# UV-Calibrator-Schematic.net
KiCad netlist of a schematic drawn in Altium Designer
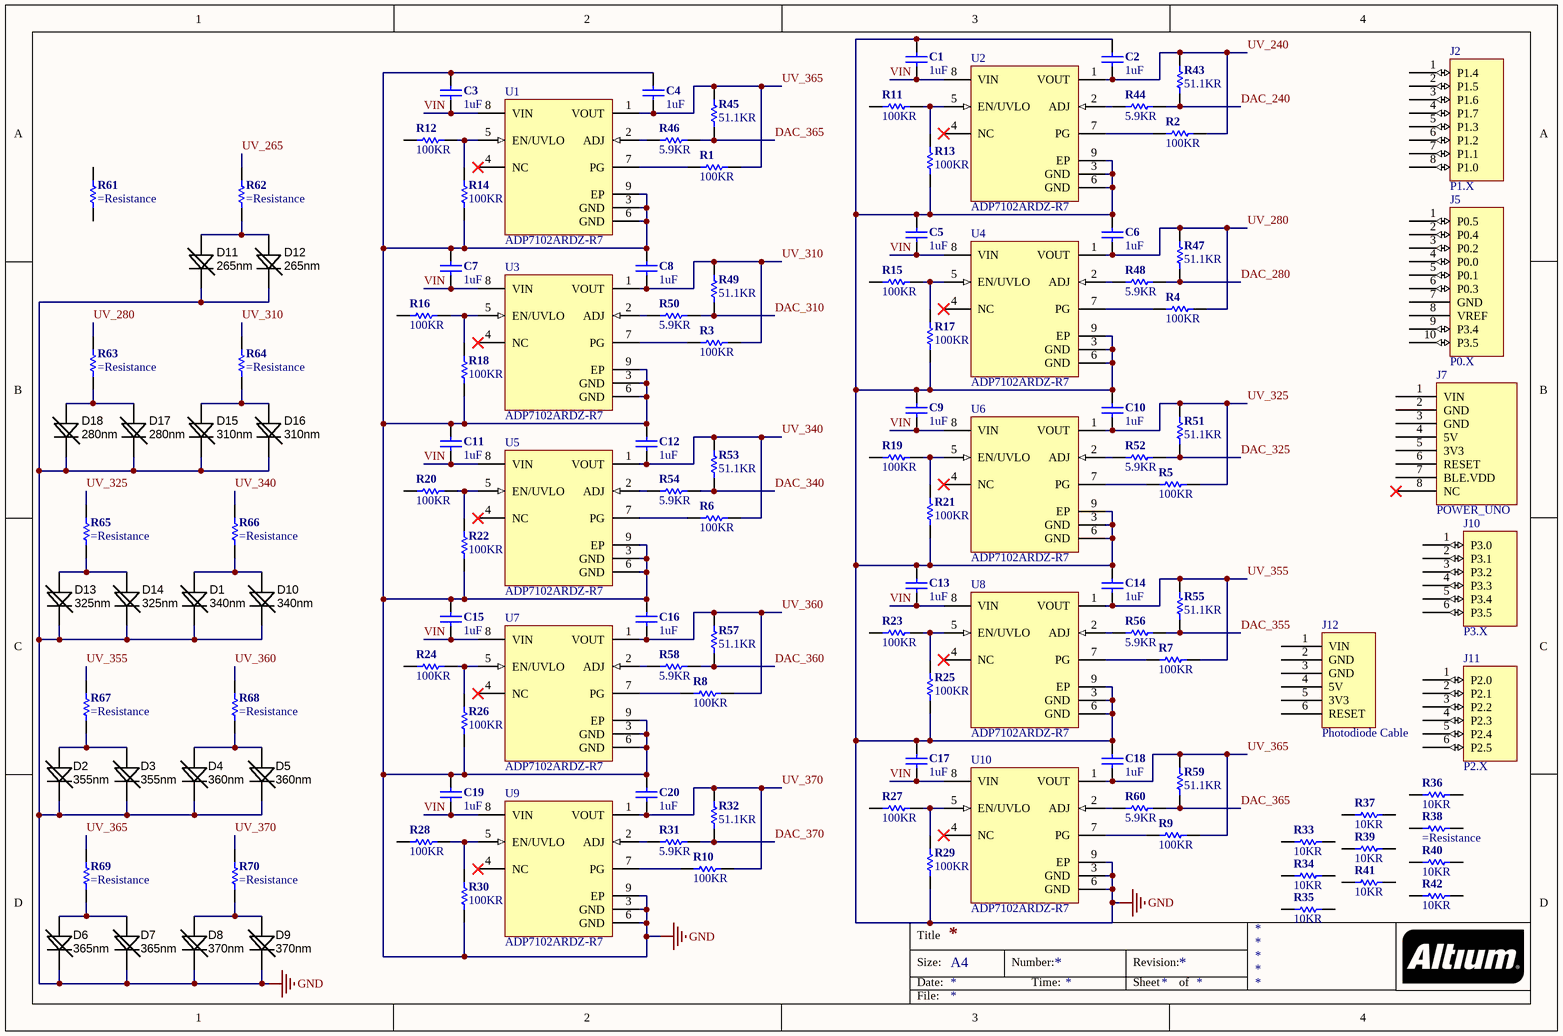
[diagram p0: UV-Calibrator-Schematic.SchDoc]

(export (version "E")
  (design (tool "Eeschema 10.0.6"))
  (components
    (comp (ref "C1")
      (value "1uF")
      (footprint "CAP-0805(2012)-R")
      (description "___ OHM ___ mW 0805(2012) SMD")
      (fields
        (field (name "MANUFACTURER") "Yageo")
        (field (name "MANUFACTURER PART NUMBER") "CC0805KKX7R7BB105")
      )
      (libsource (lib "UVS-Schlib") (part "C-0805(2012)"))
    )
    (comp (ref "C2")
      (value "1uF")
      (footprint "CAP-0805(2012)-R")
      (description "___ OHM ___ mW 0805(2012) SMD")
      (fields
        (field (name "MANUFACTURER") "Yageo")
        (field (name "MANUFACTURER PART NUMBER") "CC0805KKX7R7BB105")
      )
      (libsource (lib "UVS-Schlib") (part "C-0805(2012)"))
    )
    (comp (ref "C3")
      (value "1uF")
      (footprint "CAP-0805(2012)-R")
      (description "___ OHM ___ mW 0805(2012) SMD")
      (fields
        (field (name "MANUFACTURER") "Yageo")
        (field (name "MANUFACTURER PART NUMBER") "CC0805KKX7R7BB105")
      )
      (libsource (lib "UVS-Schlib") (part "C-0805(2012)"))
    )
    (comp (ref "C4")
      (value "1uF")
      (footprint "CAP-0805(2012)-R")
      (description "___ OHM ___ mW 0805(2012) SMD")
      (fields
        (field (name "MANUFACTURER") "Yageo")
        (field (name "MANUFACTURER PART NUMBER") "CC0805KKX7R7BB105")
      )
      (libsource (lib "UVS-Schlib") (part "C-0805(2012)"))
    )
    (comp (ref "C5")
      (value "1uF")
      (footprint "CAP-0805(2012)-R")
      (description "___ OHM ___ mW 0805(2012) SMD")
      (fields
        (field (name "MANUFACTURER") "Yageo")
        (field (name "MANUFACTURER PART NUMBER") "CC0805KKX7R7BB105")
      )
      (libsource (lib "UVS-Schlib") (part "C-0805(2012)"))
    )
    (comp (ref "C6")
      (value "1uF")
      (footprint "CAP-0805(2012)-R")
      (description "___ OHM ___ mW 0805(2012) SMD")
      (fields
        (field (name "MANUFACTURER") "Yageo")
        (field (name "MANUFACTURER PART NUMBER") "CC0805KKX7R7BB105")
      )
      (libsource (lib "UVS-Schlib") (part "C-0805(2012)"))
    )
    (comp (ref "C7")
      (value "1uF")
      (footprint "CAP-0805(2012)-R")
      (description "___ OHM ___ mW 0805(2012) SMD")
      (fields
        (field (name "MANUFACTURER") "Yageo")
        (field (name "MANUFACTURER PART NUMBER") "CC0805KKX7R7BB105")
      )
      (libsource (lib "UVS-Schlib") (part "C-0805(2012)"))
    )
    (comp (ref "C8")
      (value "1uF")
      (footprint "CAP-0805(2012)-R")
      (description "___ OHM ___ mW 0805(2012) SMD")
      (fields
        (field (name "MANUFACTURER") "Yageo")
        (field (name "MANUFACTURER PART NUMBER") "CC0805KKX7R7BB105")
      )
      (libsource (lib "UVS-Schlib") (part "C-0805(2012)"))
    )
    (comp (ref "C9")
      (value "1uF")
      (footprint "CAP-0805(2012)-R")
      (description "___ OHM ___ mW 0805(2012) SMD")
      (fields
        (field (name "MANUFACTURER") "Yageo")
        (field (name "MANUFACTURER PART NUMBER") "CC0805KKX7R7BB105")
      )
      (libsource (lib "UVS-Schlib") (part "C-0805(2012)"))
    )
    (comp (ref "C10")
      (value "1uF")
      (footprint "CAP-0805(2012)-R")
      (description "___ OHM ___ mW 0805(2012) SMD")
      (fields
        (field (name "MANUFACTURER") "Yageo")
        (field (name "MANUFACTURER PART NUMBER") "CC0805KKX7R7BB105")
      )
      (libsource (lib "UVS-Schlib") (part "C-0805(2012)"))
    )
    (comp (ref "C11")
      (value "1uF")
      (footprint "CAP-0805(2012)-R")
      (description "___ OHM ___ mW 0805(2012) SMD")
      (fields
        (field (name "MANUFACTURER") "Yageo")
        (field (name "MANUFACTURER PART NUMBER") "CC0805KKX7R7BB105")
      )
      (libsource (lib "UVS-Schlib") (part "C-0805(2012)"))
    )
    (comp (ref "C12")
      (value "1uF")
      (footprint "CAP-0805(2012)-R")
      (description "___ OHM ___ mW 0805(2012) SMD")
      (fields
        (field (name "MANUFACTURER") "Yageo")
        (field (name "MANUFACTURER PART NUMBER") "CC0805KKX7R7BB105")
      )
      (libsource (lib "UVS-Schlib") (part "C-0805(2012)"))
    )
    (comp (ref "C13")
      (value "1uF")
      (footprint "CAP-0805(2012)-R")
      (description "___ OHM ___ mW 0805(2012) SMD")
      (fields
        (field (name "MANUFACTURER") "Yageo")
        (field (name "MANUFACTURER PART NUMBER") "CC0805KKX7R7BB105")
      )
      (libsource (lib "UVS-Schlib") (part "C-0805(2012)"))
    )
    (comp (ref "C14")
      (value "1uF")
      (footprint "CAP-0805(2012)-R")
      (description "___ OHM ___ mW 0805(2012) SMD")
      (fields
        (field (name "MANUFACTURER") "Yageo")
        (field (name "MANUFACTURER PART NUMBER") "CC0805KKX7R7BB105")
      )
      (libsource (lib "UVS-Schlib") (part "C-0805(2012)"))
    )
    (comp (ref "C15")
      (value "1uF")
      (footprint "CAP-0805(2012)-R")
      (description "___ OHM ___ mW 0805(2012) SMD")
      (fields
        (field (name "MANUFACTURER") "Yageo")
        (field (name "MANUFACTURER PART NUMBER") "CC0805KKX7R7BB105")
      )
      (libsource (lib "UVS-Schlib") (part "C-0805(2012)"))
    )
    (comp (ref "C16")
      (value "1uF")
      (footprint "CAP-0805(2012)-R")
      (description "___ OHM ___ mW 0805(2012) SMD")
      (fields
        (field (name "MANUFACTURER") "Yageo")
        (field (name "MANUFACTURER PART NUMBER") "CC0805KKX7R7BB105")
      )
      (libsource (lib "UVS-Schlib") (part "C-0805(2012)"))
    )
    (comp (ref "C17")
      (value "1uF")
      (footprint "CAP-0805(2012)-R")
      (description "___ OHM ___ mW 0805(2012) SMD")
      (fields
        (field (name "MANUFACTURER") "Yageo")
        (field (name "MANUFACTURER PART NUMBER") "CC0805KKX7R7BB105")
      )
      (libsource (lib "UVS-Schlib") (part "C-0805(2012)"))
    )
    (comp (ref "C18")
      (value "1uF")
      (footprint "CAP-0805(2012)-R")
      (description "___ OHM ___ mW 0805(2012) SMD")
      (fields
        (field (name "MANUFACTURER") "Yageo")
        (field (name "MANUFACTURER PART NUMBER") "CC0805KKX7R7BB105")
      )
      (libsource (lib "UVS-Schlib") (part "C-0805(2012)"))
    )
    (comp (ref "C19")
      (value "1uF")
      (footprint "CAP-0805(2012)-R")
      (description "___ OHM ___ mW 0805(2012) SMD")
      (fields
        (field (name "MANUFACTURER") "Yageo")
        (field (name "MANUFACTURER PART NUMBER") "CC0805KKX7R7BB105")
      )
      (libsource (lib "UVS-Schlib") (part "C-0805(2012)"))
    )
    (comp (ref "C20")
      (value "1uF")
      (footprint "CAP-0805(2012)-R")
      (description "___ OHM ___ mW 0805(2012) SMD")
      (fields
        (field (name "MANUFACTURER") "Yageo")
        (field (name "MANUFACTURER PART NUMBER") "CC0805KKX7R7BB105")
      )
      (libsource (lib "UVS-Schlib") (part "C-0805(2012)"))
    )
    (comp (ref "D1")
      (value "340nm")
      (footprint "SMD 3020")
      (description "SMD 3020 UV Wavelength")
      (libsource (lib "UVS-Schlib") (part "DUVxxx-SMD"))
    )
    (comp (ref "D2")
      (value "355nm")
      (footprint "3mm LED")
      (description "LED, Through Hole 3mm")
      (libsource (lib "UVS-Schlib") (part "XSL-365-LED"))
    )
    (comp (ref "D3")
      (value "355nm")
      (footprint "3mm LED")
      (description "LED, Through Hole 3mm")
      (libsource (lib "UVS-Schlib") (part "XSL-365-LED"))
    )
    (comp (ref "D4")
      (value "360nm")
      (footprint "3mm LED")
      (description "LED, Through Hole 3mm")
      (libsource (lib "UVS-Schlib") (part "XSL-365-LED"))
    )
    (comp (ref "D5")
      (value "360nm")
      (footprint "3mm LED")
      (description "LED, Through Hole 3mm")
      (libsource (lib "UVS-Schlib") (part "XSL-365-LED"))
    )
    (comp (ref "D6")
      (value "365nm")
      (footprint "3mm LED")
      (description "LED, Through Hole 3mm")
      (libsource (lib "UVS-Schlib") (part "XSL-365-LED"))
    )
    (comp (ref "D7")
      (value "365nm")
      (footprint "3mm LED")
      (description "LED, Through Hole 3mm")
      (libsource (lib "UVS-Schlib") (part "XSL-365-LED"))
    )
    (comp (ref "D8")
      (value "370nm")
      (footprint "3mm LED")
      (description "LED, Through Hole 3mm")
      (libsource (lib "UVS-Schlib") (part "XSL-365-LED"))
    )
    (comp (ref "D9")
      (value "370nm")
      (footprint "3mm LED")
      (description "LED, Through Hole 3mm")
      (libsource (lib "UVS-Schlib") (part "XSL-365-LED"))
    )
    (comp (ref "D10")
      (value "340nm")
      (footprint "SMD 3020")
      (description "SMD 3020 UV Wavelength")
      (libsource (lib "UVS-Schlib") (part "DUVxxx-SMD"))
    )
    (comp (ref "D11")
      (value "265nm")
      (footprint "SMD 3020")
      (description "SMD 3020 UV Wavelength")
      (libsource (lib "UVS-Schlib") (part "DUVxxx-SMD"))
    )
    (comp (ref "D12")
      (value "265nm")
      (footprint "SMD 3020")
      (description "SMD 3020 UV Wavelength")
      (libsource (lib "UVS-Schlib") (part "DUVxxx-SMD"))
    )
    (comp (ref "D13")
      (value "325nm")
      (footprint "SMD 3020")
      (description "SMD 3020 UV Wavelength")
      (libsource (lib "UVS-Schlib") (part "DUVxxx-SMD"))
    )
    (comp (ref "D14")
      (value "325nm")
      (footprint "SMD 3020")
      (description "SMD 3020 UV Wavelength")
      (libsource (lib "UVS-Schlib") (part "DUVxxx-SMD"))
    )
    (comp (ref "D15")
      (value "310nm")
      (footprint "SMD 3020")
      (description "SMD 3020 UV Wavelength")
      (libsource (lib "UVS-Schlib") (part "DUVxxx-SMD"))
    )
    (comp (ref "D16")
      (value "310nm")
      (footprint "SMD 3020")
      (description "SMD 3020 UV Wavelength")
      (libsource (lib "UVS-Schlib") (part "DUVxxx-SMD"))
    )
    (comp (ref "D17")
      (value "280nm")
      (footprint "SMD 3020")
      (description "SMD 3020 UV Wavelength")
      (libsource (lib "UVS-Schlib") (part "DUVxxx-SMD"))
    )
    (comp (ref "D18")
      (value "280nm")
      (footprint "SMD 3020")
      (description "SMD 3020 UV Wavelength")
      (libsource (lib "UVS-Schlib") (part "DUVxxx-SMD"))
    )
    (comp (ref "J2")
      (value "P1.X")
      (footprint "Header 8x1 8.5mm")
      (libsource (lib "UVS-Schlib") (part "IOL"))
    )
    (comp (ref "J5")
      (value "P0.X")
      (footprint "Header 10x1 8.5mm")
      (libsource (lib "UVS-Schlib") (part "IOH"))
    )
    (comp (ref "J7")
      (value "POWER_UNO")
      (footprint "Header 8x1 8.5mm")
      (libsource (lib "UVS-Schlib") (part "POWER_UNO"))
    )
    (comp (ref "J10")
      (value "P3.X")
      (footprint "Header 6x1 8.5mm")
      (libsource (lib "UVS-Schlib") (part "AD"))
    )
    (comp (ref "J11")
      (value "P2.X")
      (footprint "Header 6x1 8.5mm")
      (libsource (lib "UVS-Schlib") (part "P2.X"))
    )
    (comp (ref "J12")
      (value "Photodiode Cable")
      (footprint "Header 6x1 8.5mm")
      (libsource (lib "UVS-Schlib") (part "PD_Calibration"))
    )
    (comp (ref "R1")
      (value "100KR")
      (footprint "R-0805(2012)-R")
      (description "___ OHM ___ mW 0805(2012) SMD")
      (fields
        (field (name "MANUFACTURER") "Yageo")
        (field (name "MANUFACTURER PART NUMBER") "RC0805FR-07100KL")
      )
      (libsource (lib "UVS-Schlib") (part "R-0805(2012)"))
    )
    (comp (ref "R2")
      (value "100KR")
      (footprint "R-0805(2012)-R")
      (description "___ OHM ___ mW 0805(2012) SMD")
      (fields
        (field (name "MANUFACTURER") "Yageo")
        (field (name "MANUFACTURER PART NUMBER") "RC0805FR-07100KL")
      )
      (libsource (lib "UVS-Schlib") (part "R-0805(2012)"))
    )
    (comp (ref "R3")
      (value "100KR")
      (footprint "R-0805(2012)-R")
      (description "___ OHM ___ mW 0805(2012) SMD")
      (fields
        (field (name "MANUFACTURER") "Yageo")
        (field (name "MANUFACTURER PART NUMBER") "RC0805FR-07100KL")
      )
      (libsource (lib "UVS-Schlib") (part "R-0805(2012)"))
    )
    (comp (ref "R4")
      (value "100KR")
      (footprint "R-0805(2012)-R")
      (description "___ OHM ___ mW 0805(2012) SMD")
      (fields
        (field (name "MANUFACTURER") "Yageo")
        (field (name "MANUFACTURER PART NUMBER") "RC0805FR-07100KL")
      )
      (libsource (lib "UVS-Schlib") (part "R-0805(2012)"))
    )
    (comp (ref "R5")
      (value "100KR")
      (footprint "R-0805(2012)-R")
      (description "___ OHM ___ mW 0805(2012) SMD")
      (fields
        (field (name "MANUFACTURER") "Yageo")
        (field (name "MANUFACTURER PART NUMBER") "RC0805FR-07100KL")
      )
      (libsource (lib "UVS-Schlib") (part "R-0805(2012)"))
    )
    (comp (ref "R6")
      (value "100KR")
      (footprint "R-0805(2012)-R")
      (description "___ OHM ___ mW 0805(2012) SMD")
      (fields
        (field (name "MANUFACTURER") "Yageo")
        (field (name "MANUFACTURER PART NUMBER") "RC0805FR-07100KL")
      )
      (libsource (lib "UVS-Schlib") (part "R-0805(2012)"))
    )
    (comp (ref "R7")
      (value "100KR")
      (footprint "R-0805(2012)-R")
      (description "___ OHM ___ mW 0805(2012) SMD")
      (fields
        (field (name "MANUFACTURER") "Yageo")
        (field (name "MANUFACTURER PART NUMBER") "RC0805FR-07100KL")
      )
      (libsource (lib "UVS-Schlib") (part "R-0805(2012)"))
    )
    (comp (ref "R8")
      (value "100KR")
      (footprint "R-0805(2012)-R")
      (description "___ OHM ___ mW 0805(2012) SMD")
      (fields
        (field (name "MANUFACTURER") "Yageo")
        (field (name "MANUFACTURER PART NUMBER") "RC0805FR-07100KL")
      )
      (libsource (lib "UVS-Schlib") (part "R-0805(2012)"))
    )
    (comp (ref "R9")
      (value "100KR")
      (footprint "R-0805(2012)-R")
      (description "___ OHM ___ mW 0805(2012) SMD")
      (fields
        (field (name "MANUFACTURER") "Yageo")
        (field (name "MANUFACTURER PART NUMBER") "RC0805FR-07100KL")
      )
      (libsource (lib "UVS-Schlib") (part "R-0805(2012)"))
    )
    (comp (ref "R10")
      (value "100KR")
      (footprint "R-0805(2012)-R")
      (description "___ OHM ___ mW 0805(2012) SMD")
      (fields
        (field (name "MANUFACTURER") "Yageo")
        (field (name "MANUFACTURER PART NUMBER") "RC0805FR-07100KL")
      )
      (libsource (lib "UVS-Schlib") (part "R-0805(2012)"))
    )
    (comp (ref "R11")
      (value "100KR")
      (footprint "R-0805(2012)-R")
      (description "___ OHM ___ mW 0805(2012) SMD")
      (fields
        (field (name "MANUFACTURER") "Yageo")
        (field (name "MANUFACTURER PART NUMBER") "RC0805FR-07100KL")
      )
      (libsource (lib "UVS-Schlib") (part "R-0805(2012)"))
    )
    (comp (ref "R12")
      (value "100KR")
      (footprint "R-0805(2012)-R")
      (description "___ OHM ___ mW 0805(2012) SMD")
      (fields
        (field (name "MANUFACTURER") "Yageo")
        (field (name "MANUFACTURER PART NUMBER") "RC0805FR-07100KL")
      )
      (libsource (lib "UVS-Schlib") (part "R-0805(2012)"))
    )
    (comp (ref "R13")
      (value "100KR")
      (footprint "R-0805(2012)-R")
      (description "___ OHM ___ mW 0805(2012) SMD")
      (fields
        (field (name "MANUFACTURER") "Yageo")
        (field (name "MANUFACTURER PART NUMBER") "RC0805FR-07100KL")
      )
      (libsource (lib "UVS-Schlib") (part "R-0805(2012)"))
    )
    (comp (ref "R14")
      (value "100KR")
      (footprint "R-0805(2012)-R")
      (description "___ OHM ___ mW 0805(2012) SMD")
      (fields
        (field (name "MANUFACTURER") "Yageo")
        (field (name "MANUFACTURER PART NUMBER") "RC0805FR-07100KL")
      )
      (libsource (lib "UVS-Schlib") (part "R-0805(2012)"))
    )
    (comp (ref "R15")
      (value "100KR")
      (footprint "R-0805(2012)-R")
      (description "___ OHM ___ mW 0805(2012) SMD")
      (fields
        (field (name "MANUFACTURER") "Yageo")
        (field (name "MANUFACTURER PART NUMBER") "RC0805FR-07100KL")
      )
      (libsource (lib "UVS-Schlib") (part "R-0805(2012)"))
    )
    (comp (ref "R16")
      (value "100KR")
      (footprint "R-0805(2012)-R")
      (description "___ OHM ___ mW 0805(2012) SMD")
      (fields
        (field (name "MANUFACTURER") "Yageo")
        (field (name "MANUFACTURER PART NUMBER") "RC0805FR-07100KL")
      )
      (libsource (lib "UVS-Schlib") (part "R-0805(2012)"))
    )
    (comp (ref "R17")
      (value "100KR")
      (footprint "R-0805(2012)-R")
      (description "___ OHM ___ mW 0805(2012) SMD")
      (fields
        (field (name "MANUFACTURER") "Yageo")
        (field (name "MANUFACTURER PART NUMBER") "RC0805FR-07100KL")
      )
      (libsource (lib "UVS-Schlib") (part "R-0805(2012)"))
    )
    (comp (ref "R18")
      (value "100KR")
      (footprint "R-0805(2012)-R")
      (description "___ OHM ___ mW 0805(2012) SMD")
      (fields
        (field (name "MANUFACTURER") "Yageo")
        (field (name "MANUFACTURER PART NUMBER") "RC0805FR-07100KL")
      )
      (libsource (lib "UVS-Schlib") (part "R-0805(2012)"))
    )
    (comp (ref "R19")
      (value "100KR")
      (footprint "R-0805(2012)-R")
      (description "___ OHM ___ mW 0805(2012) SMD")
      (fields
        (field (name "MANUFACTURER") "Yageo")
        (field (name "MANUFACTURER PART NUMBER") "RC0805FR-07100KL")
      )
      (libsource (lib "UVS-Schlib") (part "R-0805(2012)"))
    )
    (comp (ref "R20")
      (value "100KR")
      (footprint "R-0805(2012)-R")
      (description "___ OHM ___ mW 0805(2012) SMD")
      (fields
        (field (name "MANUFACTURER") "Yageo")
        (field (name "MANUFACTURER PART NUMBER") "RC0805FR-07100KL")
      )
      (libsource (lib "UVS-Schlib") (part "R-0805(2012)"))
    )
    (comp (ref "R21")
      (value "100KR")
      (footprint "R-0805(2012)-R")
      (description "___ OHM ___ mW 0805(2012) SMD")
      (fields
        (field (name "MANUFACTURER") "Yageo")
        (field (name "MANUFACTURER PART NUMBER") "RC0805FR-07100KL")
      )
      (libsource (lib "UVS-Schlib") (part "R-0805(2012)"))
    )
    (comp (ref "R22")
      (value "100KR")
      (footprint "R-0805(2012)-R")
      (description "___ OHM ___ mW 0805(2012) SMD")
      (fields
        (field (name "MANUFACTURER") "Yageo")
        (field (name "MANUFACTURER PART NUMBER") "RC0805FR-07100KL")
      )
      (libsource (lib "UVS-Schlib") (part "R-0805(2012)"))
    )
    (comp (ref "R23")
      (value "100KR")
      (footprint "R-0805(2012)-R")
      (description "___ OHM ___ mW 0805(2012) SMD")
      (fields
        (field (name "MANUFACTURER") "Yageo")
        (field (name "MANUFACTURER PART NUMBER") "RC0805FR-07100KL")
      )
      (libsource (lib "UVS-Schlib") (part "R-0805(2012)"))
    )
    (comp (ref "R24")
      (value "100KR")
      (footprint "R-0805(2012)-R")
      (description "___ OHM ___ mW 0805(2012) SMD")
      (fields
        (field (name "MANUFACTURER") "Yageo")
        (field (name "MANUFACTURER PART NUMBER") "RC0805FR-07100KL")
      )
      (libsource (lib "UVS-Schlib") (part "R-0805(2012)"))
    )
    (comp (ref "R25")
      (value "100KR")
      (footprint "R-0805(2012)-R")
      (description "___ OHM ___ mW 0805(2012) SMD")
      (fields
        (field (name "MANUFACTURER") "Yageo")
        (field (name "MANUFACTURER PART NUMBER") "RC0805FR-07100KL")
      )
      (libsource (lib "UVS-Schlib") (part "R-0805(2012)"))
    )
    (comp (ref "R26")
      (value "100KR")
      (footprint "R-0805(2012)-R")
      (description "___ OHM ___ mW 0805(2012) SMD")
      (fields
        (field (name "MANUFACTURER") "Yageo")
        (field (name "MANUFACTURER PART NUMBER") "RC0805FR-07100KL")
      )
      (libsource (lib "UVS-Schlib") (part "R-0805(2012)"))
    )
    (comp (ref "R27")
      (value "100KR")
      (footprint "R-0805(2012)-R")
      (description "___ OHM ___ mW 0805(2012) SMD")
      (fields
        (field (name "MANUFACTURER") "Yageo")
        (field (name "MANUFACTURER PART NUMBER") "RC0805FR-07100KL")
      )
      (libsource (lib "UVS-Schlib") (part "R-0805(2012)"))
    )
    (comp (ref "R28")
      (value "100KR")
      (footprint "R-0805(2012)-R")
      (description "___ OHM ___ mW 0805(2012) SMD")
      (fields
        (field (name "MANUFACTURER") "Yageo")
        (field (name "MANUFACTURER PART NUMBER") "RC0805FR-07100KL")
      )
      (libsource (lib "UVS-Schlib") (part "R-0805(2012)"))
    )
    (comp (ref "R29")
      (value "100KR")
      (footprint "R-0805(2012)-R")
      (description "___ OHM ___ mW 0805(2012) SMD")
      (fields
        (field (name "MANUFACTURER") "Yageo")
        (field (name "MANUFACTURER PART NUMBER") "RC0805FR-07100KL")
      )
      (libsource (lib "UVS-Schlib") (part "R-0805(2012)"))
    )
    (comp (ref "R30")
      (value "100KR")
      (footprint "R-0805(2012)-R")
      (description "___ OHM ___ mW 0805(2012) SMD")
      (fields
        (field (name "MANUFACTURER") "Yageo")
        (field (name "MANUFACTURER PART NUMBER") "RC0805FR-07100KL")
      )
      (libsource (lib "UVS-Schlib") (part "R-0805(2012)"))
    )
    (comp (ref "R31")
      (value "5.9KR")
      (footprint "R-0805(2012)-R")
      (description "___ OHM ___ mW 0805(2012) SMD")
      (fields
        (field (name "MANUFACTURER") "Yageo")
        (field (name "MANUFACTURER PART NUMBER") "RC0805FR-075K9L")
      )
      (libsource (lib "UVS-Schlib") (part "R-0805(2012)"))
    )
    (comp (ref "R32")
      (value "51.1KR")
      (footprint "R-0805(2012)-R")
      (description "___ OHM ___ mW 0805(2012) SMD")
      (fields
        (field (name "MANUFACTURER") "Yageo")
        (field (name "MANUFACTURER PART NUMBER") "RC0805FR-0751K1L")
      )
      (libsource (lib "UVS-Schlib") (part "R-0805(2012)"))
    )
    (comp (ref "R33")
      (value "10KR")
      (footprint "R-0805(2012)-R")
      (description "___ OHM ___ mW 0805(2012) SMD")
      (fields
        (field (name "MANUFACTURER") "Yageo")
        (field (name "MANUFACTURER PART NUMBER") "RC0805FR-0710KL")
      )
      (libsource (lib "UVS-Schlib") (part "R-0805(2012)"))
    )
    (comp (ref "R34")
      (value "10KR")
      (footprint "R-0805(2012)-R")
      (description "___ OHM ___ mW 0805(2012) SMD")
      (fields
        (field (name "MANUFACTURER") "Yageo")
        (field (name "MANUFACTURER PART NUMBER") "RC0805FR-0710KL")
      )
      (libsource (lib "UVS-Schlib") (part "R-0805(2012)"))
    )
    (comp (ref "R35")
      (value "10KR")
      (footprint "R-0805(2012)-R")
      (description "___ OHM ___ mW 0805(2012) SMD")
      (fields
        (field (name "MANUFACTURER") "Yageo")
        (field (name "MANUFACTURER PART NUMBER") "RC0805FR-0710KL")
      )
      (libsource (lib "UVS-Schlib") (part "R-0805(2012)"))
    )
    (comp (ref "R36")
      (value "10KR")
      (footprint "R-0805(2012)-R")
      (description "___ OHM ___ mW 0805(2012) SMD")
      (fields
        (field (name "MANUFACTURER") "Yageo")
        (field (name "MANUFACTURER PART NUMBER") "RC0805FR-0710KL")
      )
      (libsource (lib "UVS-Schlib") (part "R-0805(2012)"))
    )
    (comp (ref "R37")
      (value "10KR")
      (footprint "R-0805(2012)-R")
      (description "___ OHM ___ mW 0805(2012) SMD")
      (fields
        (field (name "MANUFACTURER") "Yageo")
        (field (name "MANUFACTURER PART NUMBER") "RC0805FR-0710KL")
      )
      (libsource (lib "UVS-Schlib") (part "R-0805(2012)"))
    )
    (comp (ref "R38")
      (value "~")
      (footprint "R-0805(2012)-R")
      (description "___ OHM ___ mW 0805(2012) SMD")
      (libsource (lib "UVS-Schlib") (part "R-0805(2012)"))
    )
    (comp (ref "R39")
      (value "10KR")
      (footprint "R-0805(2012)-R")
      (description "___ OHM ___ mW 0805(2012) SMD")
      (fields
        (field (name "MANUFACTURER") "Yageo")
        (field (name "MANUFACTURER PART NUMBER") "RC0805FR-0710KL")
      )
      (libsource (lib "UVS-Schlib") (part "R-0805(2012)"))
    )
    (comp (ref "R40")
      (value "10KR")
      (footprint "R-0805(2012)-R")
      (description "___ OHM ___ mW 0805(2012) SMD")
      (fields
        (field (name "MANUFACTURER") "Yageo")
        (field (name "MANUFACTURER PART NUMBER") "RC0805FR-0710KL")
      )
      (libsource (lib "UVS-Schlib") (part "R-0805(2012)"))
    )
    (comp (ref "R41")
      (value "10KR")
      (footprint "R-0805(2012)-R")
      (description "___ OHM ___ mW 0805(2012) SMD")
      (fields
        (field (name "MANUFACTURER") "Yageo")
        (field (name "MANUFACTURER PART NUMBER") "RC0805FR-0710KL")
      )
      (libsource (lib "UVS-Schlib") (part "R-0805(2012)"))
    )
    (comp (ref "R42")
      (value "10KR")
      (footprint "R-0805(2012)-R")
      (description "___ OHM ___ mW 0805(2012) SMD")
      (fields
        (field (name "MANUFACTURER") "Yageo")
        (field (name "MANUFACTURER PART NUMBER") "RC0805FR-0710KL")
      )
      (libsource (lib "UVS-Schlib") (part "R-0805(2012)"))
    )
    (comp (ref "R43")
      (value "51.1KR")
      (footprint "R-0805(2012)-R")
      (description "___ OHM ___ mW 0805(2012) SMD")
      (fields
        (field (name "MANUFACTURER") "Yageo")
        (field (name "MANUFACTURER PART NUMBER") "RC0805FR-0751K1L")
      )
      (libsource (lib "UVS-Schlib") (part "R-0805(2012)"))
    )
    (comp (ref "R44")
      (value "5.9KR")
      (footprint "R-0805(2012)-R")
      (description "___ OHM ___ mW 0805(2012) SMD")
      (fields
        (field (name "MANUFACTURER") "Yageo")
        (field (name "MANUFACTURER PART NUMBER") "RC0805FR-075K9L")
      )
      (libsource (lib "UVS-Schlib") (part "R-0805(2012)"))
    )
    (comp (ref "R45")
      (value "51.1KR")
      (footprint "R-0805(2012)-R")
      (description "___ OHM ___ mW 0805(2012) SMD")
      (fields
        (field (name "MANUFACTURER") "Yageo")
        (field (name "MANUFACTURER PART NUMBER") "RC0805FR-0751K1L")
      )
      (libsource (lib "UVS-Schlib") (part "R-0805(2012)"))
    )
    (comp (ref "R46")
      (value "5.9KR")
      (footprint "R-0805(2012)-R")
      (description "___ OHM ___ mW 0805(2012) SMD")
      (fields
        (field (name "MANUFACTURER") "Yageo")
        (field (name "MANUFACTURER PART NUMBER") "RC0805FR-075K9L")
      )
      (libsource (lib "UVS-Schlib") (part "R-0805(2012)"))
    )
    (comp (ref "R47")
      (value "51.1KR")
      (footprint "R-0805(2012)-R")
      (description "___ OHM ___ mW 0805(2012) SMD")
      (fields
        (field (name "MANUFACTURER") "Yageo")
        (field (name "MANUFACTURER PART NUMBER") "RC0805FR-0751K1L")
      )
      (libsource (lib "UVS-Schlib") (part "R-0805(2012)"))
    )
    (comp (ref "R48")
      (value "5.9KR")
      (footprint "R-0805(2012)-R")
      (description "___ OHM ___ mW 0805(2012) SMD")
      (fields
        (field (name "MANUFACTURER") "Yageo")
        (field (name "MANUFACTURER PART NUMBER") "RC0805FR-075K9L")
      )
      (libsource (lib "UVS-Schlib") (part "R-0805(2012)"))
    )
    (comp (ref "R49")
      (value "51.1KR")
      (footprint "R-0805(2012)-R")
      (description "___ OHM ___ mW 0805(2012) SMD")
      (fields
        (field (name "MANUFACTURER") "Yageo")
        (field (name "MANUFACTURER PART NUMBER") "RC0805FR-0751K1L")
      )
      (libsource (lib "UVS-Schlib") (part "R-0805(2012)"))
    )
    (comp (ref "R50")
      (value "5.9KR")
      (footprint "R-0805(2012)-R")
      (description "___ OHM ___ mW 0805(2012) SMD")
      (fields
        (field (name "MANUFACTURER") "Yageo")
        (field (name "MANUFACTURER PART NUMBER") "RC0805FR-075K9L")
      )
      (libsource (lib "UVS-Schlib") (part "R-0805(2012)"))
    )
    (comp (ref "R51")
      (value "51.1KR")
      (footprint "R-0805(2012)-R")
      (description "___ OHM ___ mW 0805(2012) SMD")
      (fields
        (field (name "MANUFACTURER") "Yageo")
        (field (name "MANUFACTURER PART NUMBER") "RC0805FR-0751K1L")
      )
      (libsource (lib "UVS-Schlib") (part "R-0805(2012)"))
    )
    (comp (ref "R52")
      (value "5.9KR")
      (footprint "R-0805(2012)-R")
      (description "___ OHM ___ mW 0805(2012) SMD")
      (fields
        (field (name "MANUFACTURER") "Yageo")
        (field (name "MANUFACTURER PART NUMBER") "RC0805FR-075K9L")
      )
      (libsource (lib "UVS-Schlib") (part "R-0805(2012)"))
    )
    (comp (ref "R53")
      (value "51.1KR")
      (footprint "R-0805(2012)-R")
      (description "___ OHM ___ mW 0805(2012) SMD")
      (fields
        (field (name "MANUFACTURER") "Yageo")
        (field (name "MANUFACTURER PART NUMBER") "RC0805FR-0751K1L")
      )
      (libsource (lib "UVS-Schlib") (part "R-0805(2012)"))
    )
    (comp (ref "R54")
      (value "5.9KR")
      (footprint "R-0805(2012)-R")
      (description "___ OHM ___ mW 0805(2012) SMD")
      (fields
        (field (name "MANUFACTURER") "Yageo")
        (field (name "MANUFACTURER PART NUMBER") "RC0805FR-075K9L")
      )
      (libsource (lib "UVS-Schlib") (part "R-0805(2012)"))
    )
    (comp (ref "R55")
      (value "51.1KR")
      (footprint "R-0805(2012)-R")
      (description "___ OHM ___ mW 0805(2012) SMD")
      (fields
        (field (name "MANUFACTURER") "Yageo")
        (field (name "MANUFACTURER PART NUMBER") "RC0805FR-0751K1L")
      )
      (libsource (lib "UVS-Schlib") (part "R-0805(2012)"))
    )
    (comp (ref "R56")
      (value "5.9KR")
      (footprint "R-0805(2012)-R")
      (description "___ OHM ___ mW 0805(2012) SMD")
      (fields
        (field (name "MANUFACTURER") "Yageo")
        (field (name "MANUFACTURER PART NUMBER") "RC0805FR-075K9L")
      )
      (libsource (lib "UVS-Schlib") (part "R-0805(2012)"))
    )
    (comp (ref "R57")
      (value "51.1KR")
      (footprint "R-0805(2012)-R")
      (description "___ OHM ___ mW 0805(2012) SMD")
      (fields
        (field (name "MANUFACTURER") "Yageo")
        (field (name "MANUFACTURER PART NUMBER") "RC0805FR-0751K1L")
      )
      (libsource (lib "UVS-Schlib") (part "R-0805(2012)"))
    )
    (comp (ref "R58")
      (value "5.9KR")
      (footprint "R-0805(2012)-R")
      (description "___ OHM ___ mW 0805(2012) SMD")
      (fields
        (field (name "MANUFACTURER") "Yageo")
        (field (name "MANUFACTURER PART NUMBER") "RC0805FR-075K9L")
      )
      (libsource (lib "UVS-Schlib") (part "R-0805(2012)"))
    )
    (comp (ref "R59")
      (value "51.1KR")
      (footprint "R-0805(2012)-R")
      (description "___ OHM ___ mW 0805(2012) SMD")
      (fields
        (field (name "MANUFACTURER") "Yageo")
        (field (name "MANUFACTURER PART NUMBER") "RC0805FR-0751K1L")
      )
      (libsource (lib "UVS-Schlib") (part "R-0805(2012)"))
    )
    (comp (ref "R60")
      (value "5.9KR")
      (footprint "R-0805(2012)-R")
      (description "___ OHM ___ mW 0805(2012) SMD")
      (fields
        (field (name "MANUFACTURER") "Yageo")
        (field (name "MANUFACTURER PART NUMBER") "RC0805FR-075K9L")
      )
      (libsource (lib "UVS-Schlib") (part "R-0805(2012)"))
    )
    (comp (ref "R61")
      (value "~")
      (footprint "R-0805(2012)-R")
      (description "___ OHM ___ mW 0805(2012) SMD")
      (libsource (lib "UVS-Schlib") (part "R-0805(2012)"))
    )
    (comp (ref "R62")
      (value "~")
      (footprint "R-0805(2012)-R")
      (description "___ OHM ___ mW 0805(2012) SMD")
      (libsource (lib "UVS-Schlib") (part "R-0805(2012)"))
    )
    (comp (ref "R63")
      (value "~")
      (footprint "R-0805(2012)-R")
      (description "___ OHM ___ mW 0805(2012) SMD")
      (libsource (lib "UVS-Schlib") (part "R-0805(2012)"))
    )
    (comp (ref "R64")
      (value "~")
      (footprint "R-0805(2012)-R")
      (description "___ OHM ___ mW 0805(2012) SMD")
      (libsource (lib "UVS-Schlib") (part "R-0805(2012)"))
    )
    (comp (ref "R65")
      (value "~")
      (footprint "R-0805(2012)-R")
      (description "___ OHM ___ mW 0805(2012) SMD")
      (libsource (lib "UVS-Schlib") (part "R-0805(2012)"))
    )
    (comp (ref "R66")
      (value "~")
      (footprint "R-0805(2012)-R")
      (description "___ OHM ___ mW 0805(2012) SMD")
      (libsource (lib "UVS-Schlib") (part "R-0805(2012)"))
    )
    (comp (ref "R67")
      (value "~")
      (footprint "R-0805(2012)-R")
      (description "___ OHM ___ mW 0805(2012) SMD")
      (libsource (lib "UVS-Schlib") (part "R-0805(2012)"))
    )
    (comp (ref "R68")
      (value "~")
      (footprint "R-0805(2012)-R")
      (description "___ OHM ___ mW 0805(2012) SMD")
      (libsource (lib "UVS-Schlib") (part "R-0805(2012)"))
    )
    (comp (ref "R69")
      (value "~")
      (footprint "R-0805(2012)-R")
      (description "___ OHM ___ mW 0805(2012) SMD")
      (libsource (lib "UVS-Schlib") (part "R-0805(2012)"))
    )
    (comp (ref "R70")
      (value "~")
      (footprint "R-0805(2012)-R")
      (description "___ OHM ___ mW 0805(2012) SMD")
      (libsource (lib "UVS-Schlib") (part "R-0805(2012)"))
    )
    (comp (ref "U1")
      (value "ADP7102ARDZ-R7")
      (footprint "ADI-RD-8-2_N")
      (fields (field (name "MANUFACTURER") "Analog Devices"))
      (libsource (lib "Altium Content Vault") (part "ADI-ADP7102_A-RD-8-2"))
    )
    (comp (ref "U2")
      (value "ADP7102ARDZ-R7")
      (footprint "ADI-RD-8-2_N")
      (fields (field (name "MANUFACTURER") "Analog Devices"))
      (libsource (lib "Altium Content Vault") (part "ADI-ADP7102_A-RD-8-2"))
    )
    (comp (ref "U3")
      (value "ADP7102ARDZ-R7")
      (footprint "ADI-RD-8-2_N")
      (fields (field (name "MANUFACTURER") "Analog Devices"))
      (libsource (lib "Altium Content Vault") (part "ADI-ADP7102_A-RD-8-2"))
    )
    (comp (ref "U4")
      (value "ADP7102ARDZ-R7")
      (footprint "ADI-RD-8-2_N")
      (fields (field (name "MANUFACTURER") "Analog Devices"))
      (libsource (lib "Altium Content Vault") (part "ADI-ADP7102_A-RD-8-2"))
    )
    (comp (ref "U5")
      (value "ADP7102ARDZ-R7")
      (footprint "ADI-RD-8-2_N")
      (fields (field (name "MANUFACTURER") "Analog Devices"))
      (libsource (lib "Altium Content Vault") (part "ADI-ADP7102_A-RD-8-2"))
    )
    (comp (ref "U6")
      (value "ADP7102ARDZ-R7")
      (footprint "ADI-RD-8-2_N")
      (fields (field (name "MANUFACTURER") "Analog Devices"))
      (libsource (lib "Altium Content Vault") (part "ADI-ADP7102_A-RD-8-2"))
    )
    (comp (ref "U7")
      (value "ADP7102ARDZ-R7")
      (footprint "ADI-RD-8-2_N")
      (fields (field (name "MANUFACTURER") "Analog Devices"))
      (libsource (lib "Altium Content Vault") (part "ADI-ADP7102_A-RD-8-2"))
    )
    (comp (ref "U8")
      (value "ADP7102ARDZ-R7")
      (footprint "ADI-RD-8-2_N")
      (fields (field (name "MANUFACTURER") "Analog Devices"))
      (libsource (lib "Altium Content Vault") (part "ADI-ADP7102_A-RD-8-2"))
    )
    (comp (ref "U9")
      (value "ADP7102ARDZ-R7")
      (footprint "ADI-RD-8-2_N")
      (fields (field (name "MANUFACTURER") "Analog Devices"))
      (libsource (lib "Altium Content Vault") (part "ADI-ADP7102_A-RD-8-2"))
    )
    (comp (ref "U10")
      (value "ADP7102ARDZ-R7")
      (footprint "ADI-RD-8-2_N")
      (fields (field (name "MANUFACTURER") "Analog Devices"))
      (libsource (lib "Altium Content Vault") (part "ADI-ADP7102_A-RD-8-2"))
    )
  )
  (nets
    (net (code "1") (name "/DAC_240") (class "Default")
      (node (ref "R43") (pin "2") (pinfunction "2_2") (pintype "passive"))
      (node (ref "R44") (pin "2") (pinfunction "2_2") (pintype "passive"))
    )
    (net (code "2") (name "/DAC_280") (class "Default")
      (node (ref "R47") (pin "2") (pinfunction "2_2") (pintype "passive"))
      (node (ref "R48") (pin "2") (pinfunction "2_2") (pintype "passive"))
    )
    (net (code "3") (name "/DAC_310") (class "Default")
      (node (ref "R49") (pin "2") (pinfunction "2_2") (pintype "passive"))
      (node (ref "R50") (pin "2") (pinfunction "2_2") (pintype "passive"))
    )
    (net (code "4") (name "/DAC_325") (class "Default")
      (node (ref "R51") (pin "2") (pinfunction "2_2") (pintype "passive"))
      (node (ref "R52") (pin "2") (pinfunction "2_2") (pintype "passive"))
    )
    (net (code "5") (name "/DAC_340") (class "Default")
      (node (ref "R53") (pin "2") (pinfunction "2_2") (pintype "passive"))
      (node (ref "R54") (pin "2") (pinfunction "2_2") (pintype "passive"))
    )
    (net (code "6") (name "/DAC_355") (class "Default")
      (node (ref "R55") (pin "2") (pinfunction "2_2") (pintype "passive"))
      (node (ref "R56") (pin "2") (pinfunction "2_2") (pintype "passive"))
    )
    (net (code "7") (name "/DAC_360") (class "Default")
      (node (ref "R57") (pin "2") (pinfunction "2_2") (pintype "passive"))
      (node (ref "R58") (pin "2") (pinfunction "2_2") (pintype "passive"))
    )
    (net (code "8") (name "/DAC_365") (class "Default")
      (node (ref "R45") (pin "2") (pinfunction "2_2") (pintype "passive"))
      (node (ref "R46") (pin "2") (pinfunction "2_2") (pintype "passive"))
      (node (ref "R59") (pin "2") (pinfunction "2_2") (pintype "passive"))
      (node (ref "R60") (pin "2") (pinfunction "2_2") (pintype "passive"))
    )
    (net (code "9") (name "/DAC_370") (class "Default")
      (node (ref "R31") (pin "2") (pinfunction "2_2") (pintype "passive"))
      (node (ref "R32") (pin "2") (pinfunction "2_2") (pintype "passive"))
    )
    (net (code "10") (name "/UV_240") (class "Default")
      (node (ref "C2") (pin "2") (pinfunction "2_2") (pintype "passive"))
      (node (ref "R2") (pin "2") (pinfunction "2_2") (pintype "passive"))
      (node (ref "R43") (pin "1") (pinfunction "1_1") (pintype "passive"))
      (node (ref "U2") (pin "1") (pinfunction "VOUT_1") (pintype "power_in"))
    )
    (net (code "11") (name "/UV_265") (class "Default")
      (node (ref "R62") (pin "1") (pinfunction "1_1") (pintype "passive"))
    )
    (net (code "12") (name "/UV_280") (class "Default")
      (node (ref "C6") (pin "2") (pinfunction "2_2") (pintype "passive"))
      (node (ref "R4") (pin "2") (pinfunction "2_2") (pintype "passive"))
      (node (ref "R47") (pin "1") (pinfunction "1_1") (pintype "passive"))
      (node (ref "R63") (pin "1") (pinfunction "1_1") (pintype "passive"))
      (node (ref "U4") (pin "1") (pinfunction "VOUT_1") (pintype "power_in"))
    )
    (net (code "13") (name "/UV_310") (class "Default")
      (node (ref "C8") (pin "2") (pinfunction "2_2") (pintype "passive"))
      (node (ref "R3") (pin "2") (pinfunction "2_2") (pintype "passive"))
      (node (ref "R49") (pin "1") (pinfunction "1_1") (pintype "passive"))
      (node (ref "R64") (pin "1") (pinfunction "1_1") (pintype "passive"))
      (node (ref "U3") (pin "1") (pinfunction "VOUT_1") (pintype "power_in"))
    )
    (net (code "14") (name "/UV_325") (class "Default")
      (node (ref "C10") (pin "2") (pinfunction "2_2") (pintype "passive"))
      (node (ref "R5") (pin "2") (pinfunction "2_2") (pintype "passive"))
      (node (ref "R51") (pin "1") (pinfunction "1_1") (pintype "passive"))
      (node (ref "R65") (pin "1") (pinfunction "1_1") (pintype "passive"))
      (node (ref "U6") (pin "1") (pinfunction "VOUT_1") (pintype "power_in"))
    )
    (net (code "15") (name "/UV_340") (class "Default")
      (node (ref "C12") (pin "2") (pinfunction "2_2") (pintype "passive"))
      (node (ref "R53") (pin "1") (pinfunction "1_1") (pintype "passive"))
      (node (ref "R6") (pin "2") (pinfunction "2_2") (pintype "passive"))
      (node (ref "R66") (pin "1") (pinfunction "1_1") (pintype "passive"))
      (node (ref "U5") (pin "1") (pinfunction "VOUT_1") (pintype "power_in"))
    )
    (net (code "16") (name "/UV_355") (class "Default")
      (node (ref "C14") (pin "2") (pinfunction "2_2") (pintype "passive"))
      (node (ref "R55") (pin "1") (pinfunction "1_1") (pintype "passive"))
      (node (ref "R67") (pin "1") (pinfunction "1_1") (pintype "passive"))
      (node (ref "R7") (pin "2") (pinfunction "2_2") (pintype "passive"))
      (node (ref "U8") (pin "1") (pinfunction "VOUT_1") (pintype "power_in"))
    )
    (net (code "17") (name "/UV_360") (class "Default")
      (node (ref "C16") (pin "2") (pinfunction "2_2") (pintype "passive"))
      (node (ref "R57") (pin "1") (pinfunction "1_1") (pintype "passive"))
      (node (ref "R68") (pin "1") (pinfunction "1_1") (pintype "passive"))
      (node (ref "R8") (pin "2") (pinfunction "2_2") (pintype "passive"))
      (node (ref "U7") (pin "1") (pinfunction "VOUT_1") (pintype "power_in"))
    )
    (net (code "18") (name "/UV_365") (class "Default")
      (node (ref "C18") (pin "2") (pinfunction "2_2") (pintype "passive"))
      (node (ref "C4") (pin "2") (pinfunction "2_2") (pintype "passive"))
      (node (ref "R1") (pin "2") (pinfunction "2_2") (pintype "passive"))
      (node (ref "R45") (pin "1") (pinfunction "1_1") (pintype "passive"))
      (node (ref "R59") (pin "1") (pinfunction "1_1") (pintype "passive"))
      (node (ref "R69") (pin "1") (pinfunction "1_1") (pintype "passive"))
      (node (ref "R9") (pin "2") (pinfunction "2_2") (pintype "passive"))
      (node (ref "U1") (pin "1") (pinfunction "VOUT_1") (pintype "power_in"))
      (node (ref "U10") (pin "1") (pinfunction "VOUT_1") (pintype "power_in"))
    )
    (net (code "19") (name "/UV_370") (class "Default")
      (node (ref "C20") (pin "2") (pinfunction "2_2") (pintype "passive"))
      (node (ref "R10") (pin "2") (pinfunction "2_2") (pintype "passive"))
      (node (ref "R32") (pin "1") (pinfunction "1_1") (pintype "passive"))
      (node (ref "R70") (pin "1") (pinfunction "1_1") (pintype "passive"))
      (node (ref "U9") (pin "1") (pinfunction "VOUT_1") (pintype "power_in"))
    )
    (net (code "20") (name "/VIN") (class "Default")
      (node (ref "C1") (pin "2") (pinfunction "2_2") (pintype "passive"))
      (node (ref "C11") (pin "2") (pinfunction "2_2") (pintype "passive"))
      (node (ref "C13") (pin "2") (pinfunction "2_2") (pintype "passive"))
      (node (ref "C15") (pin "2") (pinfunction "2_2") (pintype "passive"))
      (node (ref "C17") (pin "2") (pinfunction "2_2") (pintype "passive"))
      (node (ref "C19") (pin "2") (pinfunction "2_2") (pintype "passive"))
      (node (ref "C3") (pin "2") (pinfunction "2_2") (pintype "passive"))
      (node (ref "C5") (pin "2") (pinfunction "2_2") (pintype "passive"))
      (node (ref "C7") (pin "2") (pinfunction "2_2") (pintype "passive"))
      (node (ref "C9") (pin "2") (pinfunction "2_2") (pintype "passive"))
      (node (ref "U1") (pin "8") (pinfunction "VIN_8") (pintype "power_in"))
      (node (ref "U10") (pin "8") (pinfunction "VIN_8") (pintype "power_in"))
      (node (ref "U2") (pin "8") (pinfunction "VIN_8") (pintype "power_in"))
      (node (ref "U3") (pin "8") (pinfunction "VIN_8") (pintype "power_in"))
      (node (ref "U4") (pin "8") (pinfunction "VIN_8") (pintype "power_in"))
      (node (ref "U5") (pin "8") (pinfunction "VIN_8") (pintype "power_in"))
      (node (ref "U6") (pin "8") (pinfunction "VIN_8") (pintype "power_in"))
      (node (ref "U7") (pin "8") (pinfunction "VIN_8") (pintype "power_in"))
      (node (ref "U8") (pin "8") (pinfunction "VIN_8") (pintype "power_in"))
      (node (ref "U9") (pin "8") (pinfunction "VIN_8") (pintype "power_in"))
    )
    (net (code "21") (name "GND") (class "Default")
      (node (ref "C1") (pin "1") (pinfunction "1_1") (pintype "passive"))
      (node (ref "C10") (pin "1") (pinfunction "1_1") (pintype "passive"))
      (node (ref "C11") (pin "1") (pinfunction "1_1") (pintype "passive"))
      (node (ref "C12") (pin "1") (pinfunction "1_1") (pintype "passive"))
      (node (ref "C13") (pin "1") (pinfunction "1_1") (pintype "passive"))
      (node (ref "C14") (pin "1") (pinfunction "1_1") (pintype "passive"))
      (node (ref "C15") (pin "1") (pinfunction "1_1") (pintype "passive"))
      (node (ref "C16") (pin "1") (pinfunction "1_1") (pintype "passive"))
      (node (ref "C17") (pin "1") (pinfunction "1_1") (pintype "passive"))
      (node (ref "C18") (pin "1") (pinfunction "1_1") (pintype "passive"))
      (node (ref "C19") (pin "1") (pinfunction "1_1") (pintype "passive"))
      (node (ref "C2") (pin "1") (pinfunction "1_1") (pintype "passive"))
      (node (ref "C20") (pin "1") (pinfunction "1_1") (pintype "passive"))
      (node (ref "C3") (pin "1") (pinfunction "1_1") (pintype "passive"))
      (node (ref "C4") (pin "1") (pinfunction "1_1") (pintype "passive"))
      (node (ref "C5") (pin "1") (pinfunction "1_1") (pintype "passive"))
      (node (ref "C6") (pin "1") (pinfunction "1_1") (pintype "passive"))
      (node (ref "C7") (pin "1") (pinfunction "1_1") (pintype "passive"))
      (node (ref "C8") (pin "1") (pinfunction "1_1") (pintype "passive"))
      (node (ref "C9") (pin "1") (pinfunction "1_1") (pintype "passive"))
      (node (ref "D1") (pin "K") (pinfunction "K_K") (pintype "passive"))
      (node (ref "D10") (pin "K") (pinfunction "K_K") (pintype "passive"))
      (node (ref "D11") (pin "K") (pinfunction "K_K") (pintype "passive"))
      (node (ref "D12") (pin "K") (pinfunction "K_K") (pintype "passive"))
      (node (ref "D13") (pin "K") (pinfunction "K_K") (pintype "passive"))
      (node (ref "D14") (pin "K") (pinfunction "K_K") (pintype "passive"))
      (node (ref "D15") (pin "K") (pinfunction "K_K") (pintype "passive"))
      (node (ref "D16") (pin "K") (pinfunction "K_K") (pintype "passive"))
      (node (ref "D17") (pin "K") (pinfunction "K_K") (pintype "passive"))
      (node (ref "D18") (pin "K") (pinfunction "K_K") (pintype "passive"))
      (node (ref "D2") (pin "K") (pinfunction "K_K") (pintype "passive"))
      (node (ref "D3") (pin "K") (pinfunction "K_K") (pintype "passive"))
      (node (ref "D4") (pin "K") (pinfunction "K_K") (pintype "passive"))
      (node (ref "D5") (pin "K") (pinfunction "K_K") (pintype "passive"))
      (node (ref "D6") (pin "K") (pinfunction "K_K") (pintype "passive"))
      (node (ref "D7") (pin "K") (pinfunction "K_K") (pintype "passive"))
      (node (ref "D8") (pin "K") (pinfunction "K_K") (pintype "passive"))
      (node (ref "D9") (pin "K") (pinfunction "K_K") (pintype "passive"))
      (node (ref "R13") (pin "1") (pinfunction "1_1") (pintype "passive"))
      (node (ref "R14") (pin "1") (pinfunction "1_1") (pintype "passive"))
      (node (ref "R17") (pin "1") (pinfunction "1_1") (pintype "passive"))
      (node (ref "R18") (pin "1") (pinfunction "1_1") (pintype "passive"))
      (node (ref "R21") (pin "1") (pinfunction "1_1") (pintype "passive"))
      (node (ref "R22") (pin "1") (pinfunction "1_1") (pintype "passive"))
      (node (ref "R25") (pin "1") (pinfunction "1_1") (pintype "passive"))
      (node (ref "R26") (pin "1") (pinfunction "1_1") (pintype "passive"))
      (node (ref "R29") (pin "1") (pinfunction "1_1") (pintype "passive"))
      (node (ref "R30") (pin "1") (pinfunction "1_1") (pintype "passive"))
      (node (ref "U1") (pin "3") (pinfunction "GND_3") (pintype "power_in"))
      (node (ref "U1") (pin "6") (pinfunction "GND_6") (pintype "power_in"))
      (node (ref "U1") (pin "9") (pinfunction "EP_9") (pintype "power_in"))
      (node (ref "U10") (pin "3") (pinfunction "GND_3") (pintype "power_in"))
      (node (ref "U10") (pin "6") (pinfunction "GND_6") (pintype "power_in"))
      (node (ref "U10") (pin "9") (pinfunction "EP_9") (pintype "power_in"))
      (node (ref "U2") (pin "3") (pinfunction "GND_3") (pintype "power_in"))
      (node (ref "U2") (pin "6") (pinfunction "GND_6") (pintype "power_in"))
      (node (ref "U2") (pin "9") (pinfunction "EP_9") (pintype "power_in"))
      (node (ref "U3") (pin "3") (pinfunction "GND_3") (pintype "power_in"))
      (node (ref "U3") (pin "6") (pinfunction "GND_6") (pintype "power_in"))
      (node (ref "U3") (pin "9") (pinfunction "EP_9") (pintype "power_in"))
      (node (ref "U4") (pin "3") (pinfunction "GND_3") (pintype "power_in"))
      (node (ref "U4") (pin "6") (pinfunction "GND_6") (pintype "power_in"))
      (node (ref "U4") (pin "9") (pinfunction "EP_9") (pintype "power_in"))
      (node (ref "U5") (pin "3") (pinfunction "GND_3") (pintype "power_in"))
      (node (ref "U5") (pin "6") (pinfunction "GND_6") (pintype "power_in"))
      (node (ref "U5") (pin "9") (pinfunction "EP_9") (pintype "power_in"))
      (node (ref "U6") (pin "3") (pinfunction "GND_3") (pintype "power_in"))
      (node (ref "U6") (pin "6") (pinfunction "GND_6") (pintype "power_in"))
      (node (ref "U6") (pin "9") (pinfunction "EP_9") (pintype "power_in"))
      (node (ref "U7") (pin "3") (pinfunction "GND_3") (pintype "power_in"))
      (node (ref "U7") (pin "6") (pinfunction "GND_6") (pintype "power_in"))
      (node (ref "U7") (pin "9") (pinfunction "EP_9") (pintype "power_in"))
      (node (ref "U8") (pin "3") (pinfunction "GND_3") (pintype "power_in"))
      (node (ref "U8") (pin "6") (pinfunction "GND_6") (pintype "power_in"))
      (node (ref "U8") (pin "9") (pinfunction "EP_9") (pintype "power_in"))
      (node (ref "U9") (pin "3") (pinfunction "GND_3") (pintype "power_in"))
      (node (ref "U9") (pin "6") (pinfunction "GND_6") (pintype "power_in"))
      (node (ref "U9") (pin "9") (pinfunction "EP_9") (pintype "power_in"))
    )
    (net (code "22") (name "Net-(D1-PadA)") (class "Default")
      (node (ref "D1") (pin "A") (pinfunction "A_A") (pintype "passive"))
      (node (ref "D10") (pin "A") (pinfunction "A_A") (pintype "passive"))
      (node (ref "R66") (pin "2") (pinfunction "2_2") (pintype "passive"))
    )
    (net (code "23") (name "Net-(D2-PadA)") (class "Default")
      (node (ref "D2") (pin "A") (pinfunction "A_A") (pintype "passive"))
      (node (ref "D3") (pin "A") (pinfunction "A_A") (pintype "passive"))
      (node (ref "R67") (pin "2") (pinfunction "2_2") (pintype "passive"))
    )
    (net (code "24") (name "Net-(D4-PadA)") (class "Default")
      (node (ref "D4") (pin "A") (pinfunction "A_A") (pintype "passive"))
      (node (ref "D5") (pin "A") (pinfunction "A_A") (pintype "passive"))
      (node (ref "R68") (pin "2") (pinfunction "2_2") (pintype "passive"))
    )
    (net (code "25") (name "Net-(D6-PadA)") (class "Default")
      (node (ref "D6") (pin "A") (pinfunction "A_A") (pintype "passive"))
      (node (ref "D7") (pin "A") (pinfunction "A_A") (pintype "passive"))
      (node (ref "R69") (pin "2") (pinfunction "2_2") (pintype "passive"))
    )
    (net (code "26") (name "Net-(D8-PadA)") (class "Default")
      (node (ref "D8") (pin "A") (pinfunction "A_A") (pintype "passive"))
      (node (ref "D9") (pin "A") (pinfunction "A_A") (pintype "passive"))
      (node (ref "R70") (pin "2") (pinfunction "2_2") (pintype "passive"))
    )
    (net (code "27") (name "Net-(D11-PadA)") (class "Default")
      (node (ref "D11") (pin "A") (pinfunction "A_A") (pintype "passive"))
      (node (ref "D12") (pin "A") (pinfunction "A_A") (pintype "passive"))
      (node (ref "R62") (pin "2") (pinfunction "2_2") (pintype "passive"))
    )
    (net (code "28") (name "Net-(D13-PadA)") (class "Default")
      (node (ref "D13") (pin "A") (pinfunction "A_A") (pintype "passive"))
      (node (ref "D14") (pin "A") (pinfunction "A_A") (pintype "passive"))
      (node (ref "R65") (pin "2") (pinfunction "2_2") (pintype "passive"))
    )
    (net (code "29") (name "Net-(D15-PadA)") (class "Default")
      (node (ref "D15") (pin "A") (pinfunction "A_A") (pintype "passive"))
      (node (ref "D16") (pin "A") (pinfunction "A_A") (pintype "passive"))
      (node (ref "R64") (pin "2") (pinfunction "2_2") (pintype "passive"))
    )
    (net (code "30") (name "Net-(D17-PadA)") (class "Default")
      (node (ref "D17") (pin "A") (pinfunction "A_A") (pintype "passive"))
      (node (ref "D18") (pin "A") (pinfunction "A_A") (pintype "passive"))
      (node (ref "R63") (pin "2") (pinfunction "2_2") (pintype "passive"))
    )
    (net (code "31") (name "Net-(U1-ADJ)") (class "Default")
      (node (ref "R46") (pin "1") (pinfunction "1_1") (pintype "passive"))
      (node (ref "U1") (pin "2") (pinfunction "ADJ_2") (pintype "input"))
    )
    (net (code "32") (name "Net-(U1-EN{slash}UVLO)") (class "Default")
      (node (ref "R12") (pin "2") (pinfunction "2_2") (pintype "passive"))
      (node (ref "R14") (pin "2") (pinfunction "2_2") (pintype "passive"))
      (node (ref "U1") (pin "5") (pinfunction "EN/UVLO_5") (pintype "input"))
    )
    (net (code "33") (name "Net-(U1-PG)") (class "Default")
      (node (ref "R1") (pin "1") (pinfunction "1_1") (pintype "passive"))
      (node (ref "U1") (pin "7") (pinfunction "PG_7") (pintype "open_collector"))
    )
    (net (code "34") (name "Net-(U2-ADJ)") (class "Default")
      (node (ref "R44") (pin "1") (pinfunction "1_1") (pintype "passive"))
      (node (ref "U2") (pin "2") (pinfunction "ADJ_2") (pintype "input"))
    )
    (net (code "35") (name "Net-(U2-EN{slash}UVLO)") (class "Default")
      (node (ref "R11") (pin "2") (pinfunction "2_2") (pintype "passive"))
      (node (ref "R13") (pin "2") (pinfunction "2_2") (pintype "passive"))
      (node (ref "U2") (pin "5") (pinfunction "EN/UVLO_5") (pintype "input"))
    )
    (net (code "36") (name "Net-(U2-PG)") (class "Default")
      (node (ref "R2") (pin "1") (pinfunction "1_1") (pintype "passive"))
      (node (ref "U2") (pin "7") (pinfunction "PG_7") (pintype "open_collector"))
    )
    (net (code "37") (name "Net-(U3-ADJ)") (class "Default")
      (node (ref "R50") (pin "1") (pinfunction "1_1") (pintype "passive"))
      (node (ref "U3") (pin "2") (pinfunction "ADJ_2") (pintype "input"))
    )
    (net (code "38") (name "Net-(U3-EN{slash}UVLO)") (class "Default")
      (node (ref "R16") (pin "2") (pinfunction "2_2") (pintype "passive"))
      (node (ref "R18") (pin "2") (pinfunction "2_2") (pintype "passive"))
      (node (ref "U3") (pin "5") (pinfunction "EN/UVLO_5") (pintype "input"))
    )
    (net (code "39") (name "Net-(U3-PG)") (class "Default")
      (node (ref "R3") (pin "1") (pinfunction "1_1") (pintype "passive"))
      (node (ref "U3") (pin "7") (pinfunction "PG_7") (pintype "open_collector"))
    )
    (net (code "40") (name "Net-(U4-ADJ)") (class "Default")
      (node (ref "R48") (pin "1") (pinfunction "1_1") (pintype "passive"))
      (node (ref "U4") (pin "2") (pinfunction "ADJ_2") (pintype "input"))
    )
    (net (code "41") (name "Net-(U4-EN{slash}UVLO)") (class "Default")
      (node (ref "R15") (pin "2") (pinfunction "2_2") (pintype "passive"))
      (node (ref "R17") (pin "2") (pinfunction "2_2") (pintype "passive"))
      (node (ref "U4") (pin "5") (pinfunction "EN/UVLO_5") (pintype "input"))
    )
    (net (code "42") (name "Net-(U4-PG)") (class "Default")
      (node (ref "R4") (pin "1") (pinfunction "1_1") (pintype "passive"))
      (node (ref "U4") (pin "7") (pinfunction "PG_7") (pintype "open_collector"))
    )
    (net (code "43") (name "Net-(U5-ADJ)") (class "Default")
      (node (ref "R54") (pin "1") (pinfunction "1_1") (pintype "passive"))
      (node (ref "U5") (pin "2") (pinfunction "ADJ_2") (pintype "input"))
    )
    (net (code "44") (name "Net-(U5-EN{slash}UVLO)") (class "Default")
      (node (ref "R20") (pin "2") (pinfunction "2_2") (pintype "passive"))
      (node (ref "R22") (pin "2") (pinfunction "2_2") (pintype "passive"))
      (node (ref "U5") (pin "5") (pinfunction "EN/UVLO_5") (pintype "input"))
    )
    (net (code "45") (name "Net-(U5-PG)") (class "Default")
      (node (ref "R6") (pin "1") (pinfunction "1_1") (pintype "passive"))
      (node (ref "U5") (pin "7") (pinfunction "PG_7") (pintype "open_collector"))
    )
    (net (code "46") (name "Net-(U6-ADJ)") (class "Default")
      (node (ref "R52") (pin "1") (pinfunction "1_1") (pintype "passive"))
      (node (ref "U6") (pin "2") (pinfunction "ADJ_2") (pintype "input"))
    )
    (net (code "47") (name "Net-(U6-EN{slash}UVLO)") (class "Default")
      (node (ref "R19") (pin "2") (pinfunction "2_2") (pintype "passive"))
      (node (ref "R21") (pin "2") (pinfunction "2_2") (pintype "passive"))
      (node (ref "U6") (pin "5") (pinfunction "EN/UVLO_5") (pintype "input"))
    )
    (net (code "48") (name "Net-(U6-PG)") (class "Default")
      (node (ref "R5") (pin "1") (pinfunction "1_1") (pintype "passive"))
      (node (ref "U6") (pin "7") (pinfunction "PG_7") (pintype "open_collector"))
    )
    (net (code "49") (name "Net-(U7-ADJ)") (class "Default")
      (node (ref "R58") (pin "1") (pinfunction "1_1") (pintype "passive"))
      (node (ref "U7") (pin "2") (pinfunction "ADJ_2") (pintype "input"))
    )
    (net (code "50") (name "Net-(U7-EN{slash}UVLO)") (class "Default")
      (node (ref "R24") (pin "2") (pinfunction "2_2") (pintype "passive"))
      (node (ref "R26") (pin "2") (pinfunction "2_2") (pintype "passive"))
      (node (ref "U7") (pin "5") (pinfunction "EN/UVLO_5") (pintype "input"))
    )
    (net (code "51") (name "Net-(U7-PG)") (class "Default")
      (node (ref "R8") (pin "1") (pinfunction "1_1") (pintype "passive"))
      (node (ref "U7") (pin "7") (pinfunction "PG_7") (pintype "open_collector"))
    )
    (net (code "52") (name "Net-(U8-ADJ)") (class "Default")
      (node (ref "R56") (pin "1") (pinfunction "1_1") (pintype "passive"))
      (node (ref "U8") (pin "2") (pinfunction "ADJ_2") (pintype "input"))
    )
    (net (code "53") (name "Net-(U8-EN{slash}UVLO)") (class "Default")
      (node (ref "R23") (pin "2") (pinfunction "2_2") (pintype "passive"))
      (node (ref "R25") (pin "2") (pinfunction "2_2") (pintype "passive"))
      (node (ref "U8") (pin "5") (pinfunction "EN/UVLO_5") (pintype "input"))
    )
    (net (code "54") (name "Net-(U8-PG)") (class "Default")
      (node (ref "R7") (pin "1") (pinfunction "1_1") (pintype "passive"))
      (node (ref "U8") (pin "7") (pinfunction "PG_7") (pintype "open_collector"))
    )
    (net (code "55") (name "Net-(U9-ADJ)") (class "Default")
      (node (ref "R31") (pin "1") (pinfunction "1_1") (pintype "passive"))
      (node (ref "U9") (pin "2") (pinfunction "ADJ_2") (pintype "input"))
    )
    (net (code "56") (name "Net-(U9-EN{slash}UVLO)") (class "Default")
      (node (ref "R28") (pin "2") (pinfunction "2_2") (pintype "passive"))
      (node (ref "R30") (pin "2") (pinfunction "2_2") (pintype "passive"))
      (node (ref "U9") (pin "5") (pinfunction "EN/UVLO_5") (pintype "input"))
    )
    (net (code "57") (name "Net-(U9-PG)") (class "Default")
      (node (ref "R10") (pin "1") (pinfunction "1_1") (pintype "passive"))
      (node (ref "U9") (pin "7") (pinfunction "PG_7") (pintype "open_collector"))
    )
    (net (code "58") (name "Net-(U10-ADJ)") (class "Default")
      (node (ref "R60") (pin "1") (pinfunction "1_1") (pintype "passive"))
      (node (ref "U10") (pin "2") (pinfunction "ADJ_2") (pintype "input"))
    )
    (net (code "59") (name "Net-(U10-EN{slash}UVLO)") (class "Default")
      (node (ref "R27") (pin "2") (pinfunction "2_2") (pintype "passive"))
      (node (ref "R29") (pin "2") (pinfunction "2_2") (pintype "passive"))
      (node (ref "U10") (pin "5") (pinfunction "EN/UVLO_5") (pintype "input"))
    )
    (net (code "60") (name "Net-(U10-PG)") (class "Default")
      (node (ref "R9") (pin "1") (pinfunction "1_1") (pintype "passive"))
      (node (ref "U10") (pin "7") (pinfunction "PG_7") (pintype "open_collector"))
    )
    (net (code "61") (name "unconnected-(J2-P1.0-Pad8)") (class "Default")
      (node (ref "J2") (pin "8") (pinfunction "P1.0_8") (pintype "bidirectional"))
    )
    (net (code "62") (name "unconnected-(J2-P1.1-Pad7)") (class "Default")
      (node (ref "J2") (pin "7") (pinfunction "P1.1_7") (pintype "bidirectional"))
    )
    (net (code "63") (name "unconnected-(J2-P1.2-Pad6)") (class "Default")
      (node (ref "J2") (pin "6") (pinfunction "P1.2_6") (pintype "bidirectional"))
    )
    (net (code "64") (name "unconnected-(J2-P1.3-Pad5)") (class "Default")
      (node (ref "J2") (pin "5") (pinfunction "P1.3_5") (pintype "bidirectional"))
    )
    (net (code "65") (name "unconnected-(J2-P1.4-Pad1)") (class "Default")
      (node (ref "J2") (pin "1") (pinfunction "P1.4_1") (pintype "bidirectional"))
    )
    (net (code "66") (name "unconnected-(J2-P1.5-Pad2)") (class "Default")
      (node (ref "J2") (pin "2") (pinfunction "P1.5_2") (pintype "bidirectional"))
    )
    (net (code "67") (name "unconnected-(J2-P1.6-Pad3)") (class "Default")
      (node (ref "J2") (pin "3") (pinfunction "P1.6_3") (pintype "bidirectional"))
    )
    (net (code "68") (name "unconnected-(J2-P1.7-Pad4)") (class "Default")
      (node (ref "J2") (pin "4") (pinfunction "P1.7_4") (pintype "bidirectional"))
    )
    (net (code "69") (name "unconnected-(J5-GND-Pad7)") (class "Default")
      (node (ref "J5") (pin "7") (pinfunction "GND_7") (pintype "power_in"))
    )
    (net (code "70") (name "unconnected-(J5-P0.0-Pad4)") (class "Default")
      (node (ref "J5") (pin "4") (pinfunction "P0.0_4") (pintype "bidirectional"))
    )
    (net (code "71") (name "unconnected-(J5-P0.1-Pad5)") (class "Default")
      (node (ref "J5") (pin "5") (pinfunction "P0.1_5") (pintype "bidirectional"))
    )
    (net (code "72") (name "unconnected-(J5-P0.2-Pad3)") (class "Default")
      (node (ref "J5") (pin "3") (pinfunction "P0.2_3") (pintype "bidirectional"))
    )
    (net (code "73") (name "unconnected-(J5-P0.3-Pad6)") (class "Default")
      (node (ref "J5") (pin "6") (pinfunction "P0.3_6") (pintype "bidirectional"))
    )
    (net (code "74") (name "unconnected-(J5-P0.4-Pad2)") (class "Default")
      (node (ref "J5") (pin "2") (pinfunction "P0.4_2") (pintype "bidirectional"))
    )
    (net (code "75") (name "unconnected-(J5-P0.5-Pad1)") (class "Default")
      (node (ref "J5") (pin "1") (pinfunction "P0.5_1") (pintype "bidirectional"))
    )
    (net (code "76") (name "unconnected-(J5-P3.4-Pad9)") (class "Default")
      (node (ref "J5") (pin "9") (pinfunction "P3.4_9") (pintype "bidirectional"))
    )
    (net (code "77") (name "unconnected-(J5-P3.5-Pad10)") (class "Default")
      (node (ref "J5") (pin "10") (pinfunction "P3.5_10") (pintype "bidirectional"))
    )
    (net (code "78") (name "unconnected-(J5-VREF-Pad8)") (class "Default")
      (node (ref "J5") (pin "8") (pinfunction "VREF_8") (pintype "passive"))
    )
    (net (code "79") (name "unconnected-(J7-3V3-Pad5)") (class "Default")
      (node (ref "J7") (pin "5") (pinfunction "3V3_5") (pintype "power_in"))
    )
    (net (code "80") (name "unconnected-(J7-5V-Pad4)") (class "Default")
      (node (ref "J7") (pin "4") (pinfunction "5V_4") (pintype "power_in"))
    )
    (net (code "81") (name "unconnected-(J7-BLE.VDD-Pad7)") (class "Default")
      (node (ref "J7") (pin "7") (pinfunction "BLE.VDD_7") (pintype "power_in"))
    )
    (net (code "82") (name "unconnected-(J7-GND-Pad2)") (class "Default")
      (node (ref "J7") (pin "2") (pinfunction "GND_2") (pintype "power_in"))
    )
    (net (code "83") (name "unconnected-(J7-GND-Pad3)") (class "Default")
      (node (ref "J7") (pin "3") (pinfunction "GND_3") (pintype "power_in"))
    )
    (net (code "84") (name "unconnected-(J7-NC-Pad8)") (class "Default")
      (node (ref "J7") (pin "8") (pinfunction "NC_8") (pintype "passive+no_connect"))
    )
    (net (code "85") (name "unconnected-(J7-RESET-Pad6)") (class "Default")
      (node (ref "J7") (pin "6") (pinfunction "RESET_6") (pintype "passive"))
    )
    (net (code "86") (name "unconnected-(J7-VIN-Pad1)") (class "Default")
      (node (ref "J7") (pin "1") (pinfunction "VIN_1") (pintype "power_in"))
    )
    (net (code "87") (name "unconnected-(J10-P3.0-Pad1)") (class "Default")
      (node (ref "J10") (pin "1") (pinfunction "P3.0_1") (pintype "bidirectional"))
    )
    (net (code "88") (name "unconnected-(J10-P3.1-Pad2)") (class "Default")
      (node (ref "J10") (pin "2") (pinfunction "P3.1_2") (pintype "bidirectional"))
    )
    (net (code "89") (name "unconnected-(J10-P3.2-Pad3)") (class "Default")
      (node (ref "J10") (pin "3") (pinfunction "P3.2_3") (pintype "bidirectional"))
    )
    (net (code "90") (name "unconnected-(J10-P3.3-Pad4)") (class "Default")
      (node (ref "J10") (pin "4") (pinfunction "P3.3_4") (pintype "bidirectional"))
    )
    (net (code "91") (name "unconnected-(J10-P3.4-Pad5)") (class "Default")
      (node (ref "J10") (pin "5") (pinfunction "P3.4_5") (pintype "bidirectional"))
    )
    (net (code "92") (name "unconnected-(J10-P3.5-Pad6)") (class "Default")
      (node (ref "J10") (pin "6") (pinfunction "P3.5_6") (pintype "bidirectional"))
    )
    (net (code "93") (name "unconnected-(J11-P2.0-Pad1)") (class "Default")
      (node (ref "J11") (pin "1") (pinfunction "P2.0_1") (pintype "bidirectional"))
    )
    (net (code "94") (name "unconnected-(J11-P2.1-Pad2)") (class "Default")
      (node (ref "J11") (pin "2") (pinfunction "P2.1_2") (pintype "bidirectional"))
    )
    (net (code "95") (name "unconnected-(J11-P2.2-Pad3)") (class "Default")
      (node (ref "J11") (pin "3") (pinfunction "P2.2_3") (pintype "bidirectional"))
    )
    (net (code "96") (name "unconnected-(J11-P2.3-Pad4)") (class "Default")
      (node (ref "J11") (pin "4") (pinfunction "P2.3_4") (pintype "bidirectional"))
    )
    (net (code "97") (name "unconnected-(J11-P2.4-Pad5)") (class "Default")
      (node (ref "J11") (pin "5") (pinfunction "P2.4_5") (pintype "bidirectional"))
    )
    (net (code "98") (name "unconnected-(J11-P2.5-Pad6)") (class "Default")
      (node (ref "J11") (pin "6") (pinfunction "P2.5_6") (pintype "bidirectional"))
    )
    (net (code "99") (name "unconnected-(J12-3V3-Pad5)") (class "Default")
      (node (ref "J12") (pin "5") (pinfunction "3V3_5") (pintype "power_in"))
    )
    (net (code "100") (name "unconnected-(J12-5V-Pad4)") (class "Default")
      (node (ref "J12") (pin "4") (pinfunction "5V_4") (pintype "power_in"))
    )
    (net (code "101") (name "unconnected-(J12-GND-Pad2)") (class "Default")
      (node (ref "J12") (pin "2") (pinfunction "GND_2") (pintype "power_in"))
    )
    (net (code "102") (name "unconnected-(J12-GND-Pad3)") (class "Default")
      (node (ref "J12") (pin "3") (pinfunction "GND_3") (pintype "power_in"))
    )
    (net (code "103") (name "unconnected-(J12-RESET-Pad6)") (class "Default")
      (node (ref "J12") (pin "6") (pinfunction "RESET_6") (pintype "passive"))
    )
    (net (code "104") (name "unconnected-(J12-VIN-Pad1)") (class "Default")
      (node (ref "J12") (pin "1") (pinfunction "VIN_1") (pintype "power_in"))
    )
    (net (code "105") (name "unconnected-(R11-Pad1)") (class "Default")
      (node (ref "R11") (pin "1") (pinfunction "1_1") (pintype "passive"))
    )
    (net (code "106") (name "unconnected-(R12-Pad1)") (class "Default")
      (node (ref "R12") (pin "1") (pinfunction "1_1") (pintype "passive"))
    )
    (net (code "107") (name "unconnected-(R15-Pad1)") (class "Default")
      (node (ref "R15") (pin "1") (pinfunction "1_1") (pintype "passive"))
    )
    (net (code "108") (name "unconnected-(R16-Pad1)") (class "Default")
      (node (ref "R16") (pin "1") (pinfunction "1_1") (pintype "passive"))
    )
    (net (code "109") (name "unconnected-(R19-Pad1)") (class "Default")
      (node (ref "R19") (pin "1") (pinfunction "1_1") (pintype "passive"))
    )
    (net (code "110") (name "unconnected-(R20-Pad1)") (class "Default")
      (node (ref "R20") (pin "1") (pinfunction "1_1") (pintype "passive"))
    )
    (net (code "111") (name "unconnected-(R23-Pad1)") (class "Default")
      (node (ref "R23") (pin "1") (pinfunction "1_1") (pintype "passive"))
    )
    (net (code "112") (name "unconnected-(R24-Pad1)") (class "Default")
      (node (ref "R24") (pin "1") (pinfunction "1_1") (pintype "passive"))
    )
    (net (code "113") (name "unconnected-(R27-Pad1)") (class "Default")
      (node (ref "R27") (pin "1") (pinfunction "1_1") (pintype "passive"))
    )
    (net (code "114") (name "unconnected-(R28-Pad1)") (class "Default")
      (node (ref "R28") (pin "1") (pinfunction "1_1") (pintype "passive"))
    )
    (net (code "115") (name "unconnected-(R33-Pad1)") (class "Default")
      (node (ref "R33") (pin "1") (pinfunction "1_1") (pintype "passive"))
    )
    (net (code "116") (name "unconnected-(R33-Pad2)") (class "Default")
      (node (ref "R33") (pin "2") (pinfunction "2_2") (pintype "passive"))
    )
    (net (code "117") (name "unconnected-(R34-Pad1)") (class "Default")
      (node (ref "R34") (pin "1") (pinfunction "1_1") (pintype "passive"))
    )
    (net (code "118") (name "unconnected-(R34-Pad2)") (class "Default")
      (node (ref "R34") (pin "2") (pinfunction "2_2") (pintype "passive"))
    )
    (net (code "119") (name "unconnected-(R35-Pad1)") (class "Default")
      (node (ref "R35") (pin "1") (pinfunction "1_1") (pintype "passive"))
    )
    (net (code "120") (name "unconnected-(R35-Pad2)") (class "Default")
      (node (ref "R35") (pin "2") (pinfunction "2_2") (pintype "passive"))
    )
    (net (code "121") (name "unconnected-(R36-Pad1)") (class "Default")
      (node (ref "R36") (pin "1") (pinfunction "1_1") (pintype "passive"))
    )
    (net (code "122") (name "unconnected-(R36-Pad2)") (class "Default")
      (node (ref "R36") (pin "2") (pinfunction "2_2") (pintype "passive"))
    )
    (net (code "123") (name "unconnected-(R37-Pad1)") (class "Default")
      (node (ref "R37") (pin "1") (pinfunction "1_1") (pintype "passive"))
    )
    (net (code "124") (name "unconnected-(R37-Pad2)") (class "Default")
      (node (ref "R37") (pin "2") (pinfunction "2_2") (pintype "passive"))
    )
    (net (code "125") (name "unconnected-(R38-Pad1)") (class "Default")
      (node (ref "R38") (pin "1") (pinfunction "1_1") (pintype "passive"))
    )
    (net (code "126") (name "unconnected-(R38-Pad2)") (class "Default")
      (node (ref "R38") (pin "2") (pinfunction "2_2") (pintype "passive"))
    )
    (net (code "127") (name "unconnected-(R39-Pad1)") (class "Default")
      (node (ref "R39") (pin "1") (pinfunction "1_1") (pintype "passive"))
    )
    (net (code "128") (name "unconnected-(R39-Pad2)") (class "Default")
      (node (ref "R39") (pin "2") (pinfunction "2_2") (pintype "passive"))
    )
    (net (code "129") (name "unconnected-(R40-Pad1)") (class "Default")
      (node (ref "R40") (pin "1") (pinfunction "1_1") (pintype "passive"))
    )
    (net (code "130") (name "unconnected-(R40-Pad2)") (class "Default")
      (node (ref "R40") (pin "2") (pinfunction "2_2") (pintype "passive"))
    )
    (net (code "131") (name "unconnected-(R41-Pad1)") (class "Default")
      (node (ref "R41") (pin "1") (pinfunction "1_1") (pintype "passive"))
    )
    (net (code "132") (name "unconnected-(R41-Pad2)") (class "Default")
      (node (ref "R41") (pin "2") (pinfunction "2_2") (pintype "passive"))
    )
    (net (code "133") (name "unconnected-(R42-Pad1)") (class "Default")
      (node (ref "R42") (pin "1") (pinfunction "1_1") (pintype "passive"))
    )
    (net (code "134") (name "unconnected-(R42-Pad2)") (class "Default")
      (node (ref "R42") (pin "2") (pinfunction "2_2") (pintype "passive"))
    )
    (net (code "135") (name "unconnected-(R61-Pad1)") (class "Default")
      (node (ref "R61") (pin "1") (pinfunction "1_1") (pintype "passive"))
    )
    (net (code "136") (name "unconnected-(R61-Pad2)") (class "Default")
      (node (ref "R61") (pin "2") (pinfunction "2_2") (pintype "passive"))
    )
    (net (code "137") (name "unconnected-(U1-NC-Pad4)") (class "Default")
      (node (ref "U1") (pin "4") (pinfunction "NC_4") (pintype "passive+no_connect"))
    )
    (net (code "138") (name "unconnected-(U2-NC-Pad4)") (class "Default")
      (node (ref "U2") (pin "4") (pinfunction "NC_4") (pintype "passive+no_connect"))
    )
    (net (code "139") (name "unconnected-(U3-NC-Pad4)") (class "Default")
      (node (ref "U3") (pin "4") (pinfunction "NC_4") (pintype "passive+no_connect"))
    )
    (net (code "140") (name "unconnected-(U4-NC-Pad4)") (class "Default")
      (node (ref "U4") (pin "4") (pinfunction "NC_4") (pintype "passive+no_connect"))
    )
    (net (code "141") (name "unconnected-(U5-NC-Pad4)") (class "Default")
      (node (ref "U5") (pin "4") (pinfunction "NC_4") (pintype "passive+no_connect"))
    )
    (net (code "142") (name "unconnected-(U6-NC-Pad4)") (class "Default")
      (node (ref "U6") (pin "4") (pinfunction "NC_4") (pintype "passive+no_connect"))
    )
    (net (code "143") (name "unconnected-(U7-NC-Pad4)") (class "Default")
      (node (ref "U7") (pin "4") (pinfunction "NC_4") (pintype "passive+no_connect"))
    )
    (net (code "144") (name "unconnected-(U8-NC-Pad4)") (class "Default")
      (node (ref "U8") (pin "4") (pinfunction "NC_4") (pintype "passive+no_connect"))
    )
    (net (code "145") (name "unconnected-(U9-NC-Pad4)") (class "Default")
      (node (ref "U9") (pin "4") (pinfunction "NC_4") (pintype "passive+no_connect"))
    )
    (net (code "146") (name "unconnected-(U10-NC-Pad4)") (class "Default")
      (node (ref "U10") (pin "4") (pinfunction "NC_4") (pintype "passive+no_connect"))
    )
  )
)
